# Sheet2.net
KiCad netlist of a schematic drawn in Altium Designer
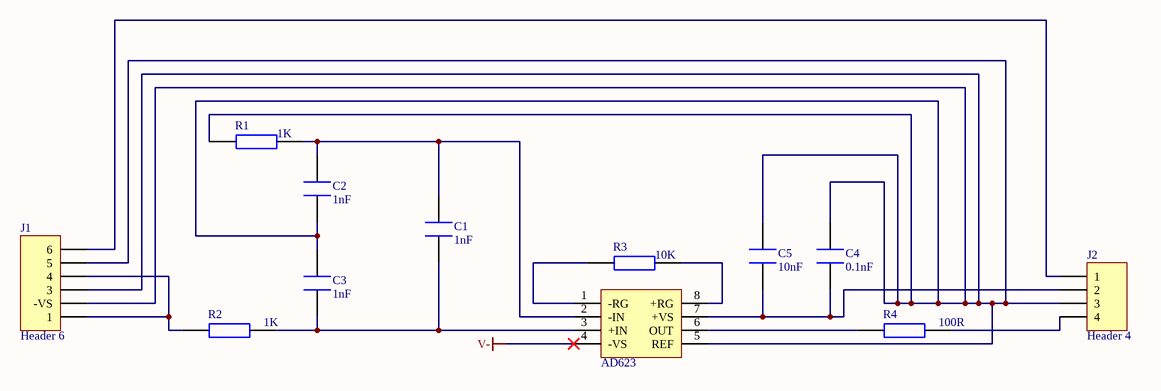
[diagram p0: Sheet2.SchDoc]

(export (version "E")
  (design (tool "Eeschema 10.0.6"))
  (components
    (comp (ref "C1")
      (value "1nF")
      (footprint "0402")
      (description "电容")
      (libsource (lib "Schlib1") (part "CAP"))
    )
    (comp (ref "C2")
      (value "1nF")
      (footprint "0402")
      (description "电容")
      (libsource (lib "Schlib1") (part "CAP"))
    )
    (comp (ref "C3")
      (value "1nF")
      (footprint "0402")
      (description "电容")
      (libsource (lib "Schlib1") (part "CAP"))
    )
    (comp (ref "C4")
      (value "0.1nF")
      (footprint "0402")
      (description "电容")
      (libsource (lib "Schlib1") (part "CAP"))
    )
    (comp (ref "C5")
      (value "10nF")
      (footprint "0402")
      (description "电容")
      (libsource (lib "Schlib1") (part "CAP"))
    )
    (comp (ref "J1")
      (value "Header 6")
      (footprint "软排线6p")
      (description "Header, 6-Pin")
      (fields (field (name "PUBLISHER") "Altium Limited"))
      (libsource (lib "Miscellaneous Connectors") (part "Header 6"))
    )
    (comp (ref "J2")
      (value "Header 4")
      (footprint "软排线4p")
      (description "Header, 4-Pin")
      (fields (field (name "PUBLISHER") "Altium Limited"))
      (libsource (lib "Miscellaneous Connectors") (part "Header 4"))
    )
    (comp (ref "R1")
      (value "1K")
      (footprint "0402-A")
      (description "电阻")
      (libsource (lib "Schlib1") (part "RES"))
    )
    (comp (ref "R2")
      (value "1K")
      (footprint "0402-A")
      (description "电阻")
      (libsource (lib "Schlib1") (part "RES"))
    )
    (comp (ref "R3")
      (value "10K")
      (footprint "0402-A")
      (description "电阻")
      (libsource (lib "Schlib1") (part "RES"))
    )
    (comp (ref "R4")
      (value "100R")
      (footprint "0402-A")
      (description "电阻")
      (libsource (lib "Schlib1") (part "RES"))
    )
    (comp (ref "U2")
      (value "AD623")
      (footprint "SO8_M")
      (description "IC")
      (libsource (lib "Schlib1") (part "AD623"))
    )
  )
  (nets
    (net (code "2") (name "Net-(J1--VS)") (class "Default")
      (node (ref "C2") (pin "1") (pinfunction "1_1") (pintype "passive"))
      (node (ref "C3") (pin "2") (pinfunction "2_2") (pintype "passive"))
      (node (ref "C4") (pin "2") (pinfunction "2_2") (pintype "passive"))
      (node (ref "C5") (pin "2") (pinfunction "2_2") (pintype "passive"))
      (node (ref "J1") (pin "2") (pinfunction "-VS_2") (pintype "passive"))
      (node (ref "J1") (pin "3") (pinfunction "3_3") (pintype "passive"))
      (node (ref "J1") (pin "5") (pinfunction "5_5") (pintype "passive"))
      (node (ref "J2") (pin "3") (pinfunction "3_3") (pintype "passive"))
      (node (ref "R1") (pin "1") (pinfunction "1_1") (pintype "passive"))
      (node (ref "U2") (pin "5") (pinfunction "REF_5") (pintype "passive"))
    )
    (net (code "3") (name "Net-(J1-Pad1)") (class "Default")
      (node (ref "J1") (pin "1") (pinfunction "1_1") (pintype "passive"))
      (node (ref "J1") (pin "4") (pinfunction "4_4") (pintype "passive"))
      (node (ref "R2") (pin "1") (pinfunction "1_1") (pintype "passive"))
    )
    (net (code "4") (name "Net-(J1-Pad6)") (class "Default")
      (node (ref "J1") (pin "6") (pinfunction "6_6") (pintype "passive"))
      (node (ref "J2") (pin "1") (pinfunction "1_1") (pintype "passive"))
    )
    (net (code "5") (name "Net-(J2-Pad4)") (class "Default")
      (node (ref "J2") (pin "4") (pinfunction "4_4") (pintype "passive"))
      (node (ref "R4") (pin "2") (pinfunction "2_2") (pintype "passive"))
    )
    (net (code "6") (name "Net-(U2-+IN)") (class "Default")
      (node (ref "C1") (pin "1") (pinfunction "1_1") (pintype "passive"))
      (node (ref "C3") (pin "1") (pinfunction "1_1") (pintype "passive"))
      (node (ref "R2") (pin "2") (pinfunction "2_2") (pintype "passive"))
      (node (ref "U2") (pin "3") (pinfunction "+IN_3") (pintype "passive"))
    )
    (net (code "7") (name "Net-(U2-+RG)") (class "Default")
      (node (ref "R3") (pin "2") (pinfunction "2_2") (pintype "passive"))
      (node (ref "U2") (pin "8") (pinfunction "+RG_8") (pintype "passive"))
    )
    (net (code "8") (name "Net-(U2-+VS)") (class "Default")
      (node (ref "C4") (pin "1") (pinfunction "1_1") (pintype "passive"))
      (node (ref "C5") (pin "1") (pinfunction "1_1") (pintype "passive"))
      (node (ref "J2") (pin "2") (pinfunction "2_2") (pintype "passive"))
      (node (ref "U2") (pin "7") (pinfunction "+VS_7") (pintype "passive"))
    )
    (net (code "9") (name "Net-(U2--IN)") (class "Default")
      (node (ref "C1") (pin "2") (pinfunction "2_2") (pintype "passive"))
      (node (ref "C2") (pin "2") (pinfunction "2_2") (pintype "passive"))
      (node (ref "R1") (pin "2") (pinfunction "2_2") (pintype "passive"))
      (node (ref "U2") (pin "2") (pinfunction "-IN_2") (pintype "passive"))
    )
    (net (code "10") (name "Net-(U2--RG)") (class "Default")
      (node (ref "R3") (pin "1") (pinfunction "1_1") (pintype "passive"))
      (node (ref "U2") (pin "1") (pinfunction "-RG_1") (pintype "passive"))
    )
    (net (code "11") (name "Net-(U2-OUT)") (class "Default")
      (node (ref "R4") (pin "1") (pinfunction "1_1") (pintype "passive"))
      (node (ref "U2") (pin "6") (pinfunction "OUT_6") (pintype "passive"))
    )
    (net (code "12") (name "V-") (class "Default")
      (node (ref "U2") (pin "4") (pinfunction "-VS_4") (pintype "passive"))
    )
  )
)
